# Button_Breakout_sch.net
KiCad netlist of a schematic drawn in Altium Designer
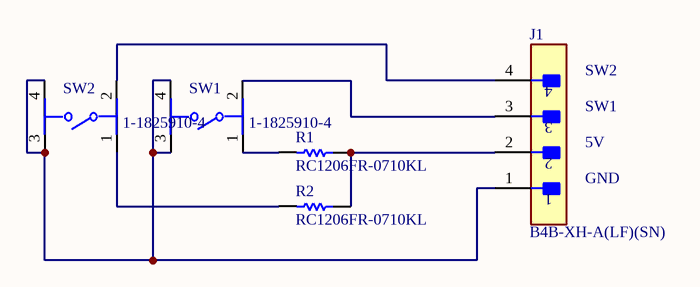
[diagram p0: Button_Breakout_sch.SchDoc]

(export (version "E")
  (design (tool "Eeschema 10.0.6"))
  (components
    (comp (ref "J1")
      (value "B4B-XH-A(LF)(SN)")
      (footprint "FP-B4B-XH-A_LF_SN-MFG")
      (description "CONN HEADER VERT 4POS 2.5MM")
      (libsource (lib "Altium Content Vault") (part "299a8cea1bdcbc3624fe62c390fa72c"))
    )
    (comp (ref "R1")
      (value "RC1206FR-0710KL")
      (footprint "RESC3116X65X40ML10T20")
      (description "Chip Resistor, 10 KOhm, +/- 1%, 0.25 W, -55 to 155 degC, 1206 (3216 Metric), RoHS, Tape and Reel")
      (fields (field (name "TOLERANCE") "1%") (field (name "MANUFACTURER") "Yageo"))
      (libsource (lib "Altium Content Vault") (part "RES-2"))
    )
    (comp (ref "R2")
      (value "RC1206FR-0710KL")
      (footprint "RESC3116X65X40ML10T20")
      (description "Chip Resistor, 10 KOhm, +/- 1%, 0.25 W, -55 to 155 degC, 1206 (3216 Metric), RoHS, Tape and Reel")
      (fields (field (name "TOLERANCE") "1%") (field (name "MANUFACTURER") "Yageo"))
      (libsource (lib "Altium Content Vault") (part "RES-2"))
    )
    (comp (ref "SW1")
      (value "1-1825910-4")
      (footprint "FP-1-1825910-4-MFG")
      (description "SWITCH TACTILE SPST-NO 0.05A 24V")
      (fields
        (field (name "OCTOPART") "https://octopart.com/1-1825910-4-te+connectivity-42270468")
        (field (name "MANUFACTURER") "TE Connectivity")
      )
      (libsource (lib "Altium Content Vault") (part "b8895f3f4cefb76e1819d2863dba89b"))
    )
    (comp (ref "SW2")
      (value "1-1825910-4")
      (footprint "FP-1-1825910-4-MFG")
      (description "SWITCH TACTILE SPST-NO 0.05A 24V")
      (fields
        (field (name "OCTOPART") "https://octopart.com/1-1825910-4-te+connectivity-42270468")
        (field (name "MANUFACTURER") "TE Connectivity")
      )
      (libsource (lib "Altium Content Vault") (part "b8895f3f4cefb76e1819d2863dba89b"))
    )
  )
  (nets
    (net (code "1") (name "Net-(J1-Pad1)") (class "Default")
      (node (ref "J1") (pin "1") (pinfunction "1_1") (pintype "passive"))
      (node (ref "SW1") (pin "3") (pinfunction "3_3") (pintype "passive"))
      (node (ref "SW1") (pin "4") (pinfunction "4_4") (pintype "passive"))
      (node (ref "SW2") (pin "3") (pinfunction "3_3") (pintype "passive"))
      (node (ref "SW2") (pin "4") (pinfunction "4_4") (pintype "passive"))
    )
    (net (code "2") (name "Net-(J1-Pad2)") (class "Default")
      (node (ref "J1") (pin "2") (pinfunction "2_2") (pintype "passive"))
      (node (ref "R1") (pin "1") (pinfunction "1_1") (pintype "passive"))
      (node (ref "R2") (pin "1") (pinfunction "1_1") (pintype "passive"))
    )
    (net (code "3") (name "Net-(J1-Pad3)") (class "Default")
      (node (ref "J1") (pin "3") (pinfunction "3_3") (pintype "passive"))
      (node (ref "SW1") (pin "2") (pinfunction "2_2") (pintype "passive"))
    )
    (net (code "4") (name "Net-(J1-Pad4)") (class "Default")
      (node (ref "J1") (pin "4") (pinfunction "4_4") (pintype "passive"))
      (node (ref "SW2") (pin "2") (pinfunction "2_2") (pintype "passive"))
    )
    (net (code "5") (name "Net-(R1-Pad2)") (class "Default")
      (node (ref "R1") (pin "2") (pinfunction "2_2") (pintype "passive"))
      (node (ref "SW1") (pin "1") (pinfunction "1_1") (pintype "passive"))
    )
    (net (code "6") (name "Net-(R2-Pad2)") (class "Default")
      (node (ref "R2") (pin "2") (pinfunction "2_2") (pintype "passive"))
      (node (ref "SW2") (pin "1") (pinfunction "1_1") (pintype "passive"))
    )
  )
)
